# 21_DAC.net
KiCad netlist of a schematic drawn in Altium Designer
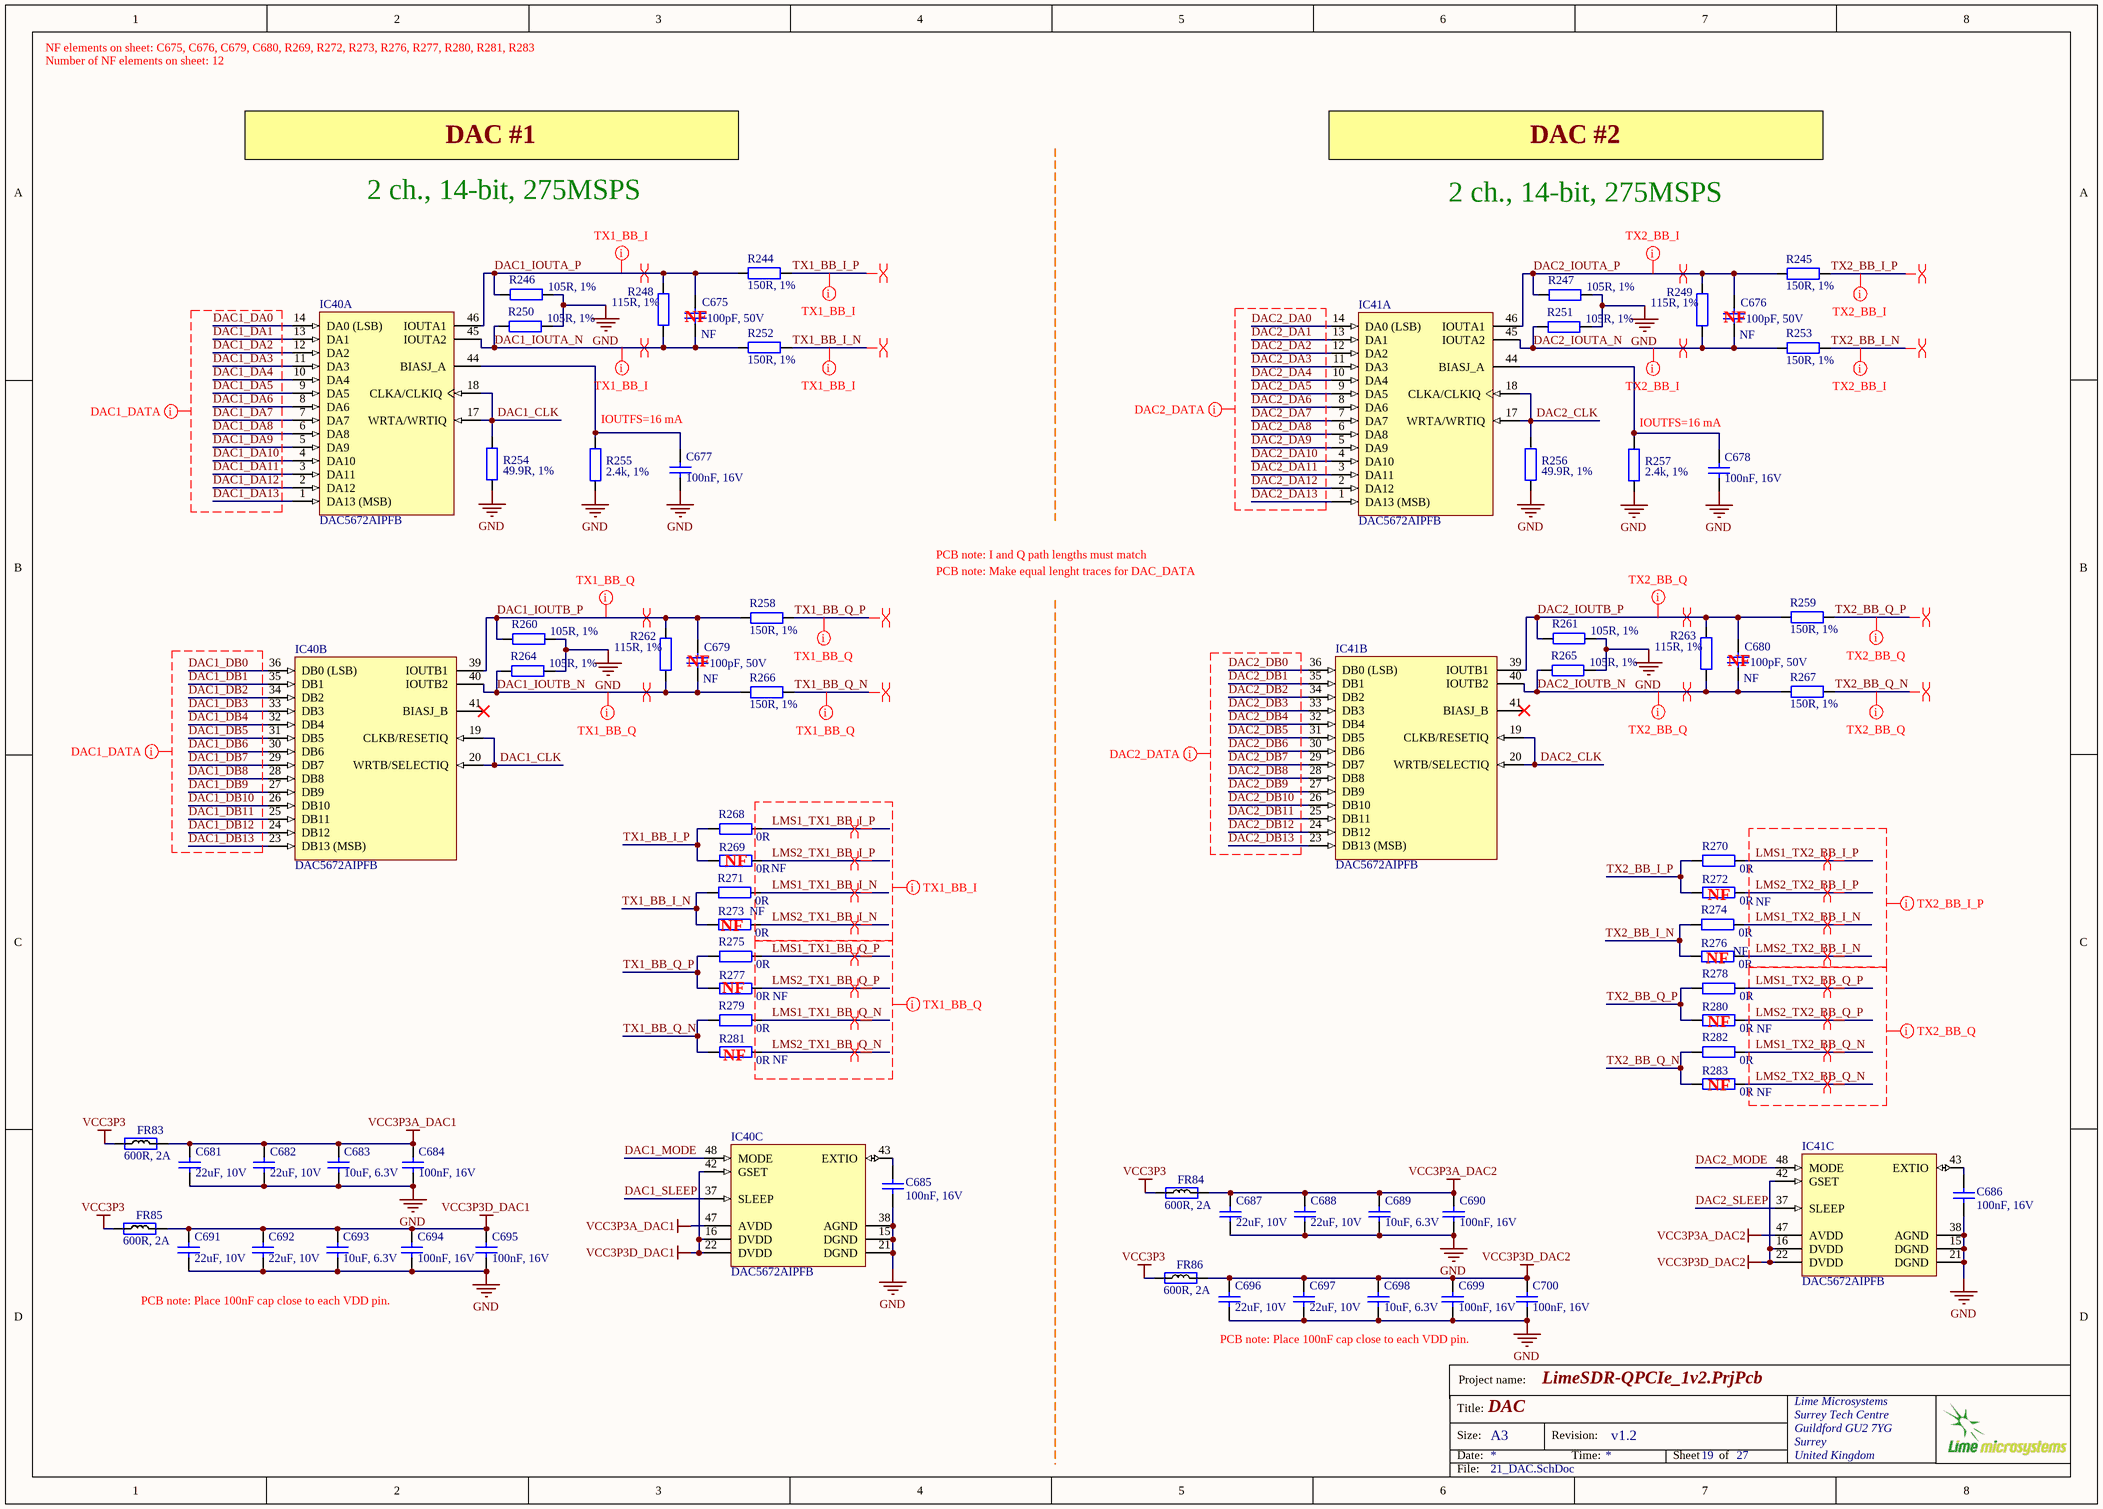
[diagram p0: 21_DAC.SchDoc]

(export (version "E")
  (design (tool "Eeschema 10.0.6"))
  (components
    (comp (ref "C675")
      (value "100pF, 50V")
      (footprint "CAP0402")
      (fields
        (field (name "ASSEMBLY INFO") "NF")
        (field (name "TOLERANCE") "±5%")
        (field (name "MANUFACTURER") "Yageo")
      )
      (libsource (lib "LimeMicroAltiumLib_schLib") (part "Cap_0402"))
    )
    (comp (ref "C676")
      (value "100pF, 50V")
      (footprint "CAP0402")
      (fields
        (field (name "ASSEMBLY INFO") "NF")
        (field (name "TOLERANCE") "±5%")
        (field (name "MANUFACTURER") "Yageo")
      )
      (libsource (lib "LimeMicroAltiumLib_schLib") (part "Cap_0402"))
    )
    (comp (ref "C677")
      (value "100nF, 16V")
      (footprint "CAP0402")
      (fields
        (field (name "TOLERANCE") "10 %")
        (field (name "MANUFACTURER") "Murata Electronics")
        (field (name "MANUFACTURER PART NUMBER") "GRM155R71C104KA88D")
      )
      (libsource (lib "LimeFPGAboard_schLib") (part "Cap_0603"))
    )
    (comp (ref "C678")
      (value "100nF, 16V")
      (footprint "CAP0402")
      (fields
        (field (name "TOLERANCE") "10 %")
        (field (name "MANUFACTURER") "Murata Electronics")
        (field (name "MANUFACTURER PART NUMBER") "GRM155R71C104KA88D")
      )
      (libsource (lib "LimeFPGAboard_schLib") (part "Cap_0603"))
    )
    (comp (ref "C679")
      (value "100pF, 50V")
      (footprint "CAP0402")
      (fields
        (field (name "ASSEMBLY INFO") "NF")
        (field (name "TOLERANCE") "±5%")
        (field (name "MANUFACTURER") "Yageo")
      )
      (libsource (lib "LimeMicroAltiumLib_schLib") (part "Cap_0402"))
    )
    (comp (ref "C680")
      (value "100pF, 50V")
      (footprint "CAP0402")
      (fields
        (field (name "ASSEMBLY INFO") "NF")
        (field (name "TOLERANCE") "±5%")
        (field (name "MANUFACTURER") "Yageo")
      )
      (libsource (lib "LimeMicroAltiumLib_schLib") (part "Cap_0402"))
    )
    (comp (ref "C681")
      (value "22uF, 10V")
      (footprint "CAP0603")
      (fields (field (name "TOLERANCE") "20 %") (field (name "MANUFACTURER") "TDK Corporation"))
      (libsource (lib "LimeFPGAboard_schLib") (part "Cap_0603"))
    )
    (comp (ref "C682")
      (value "22uF, 10V")
      (footprint "CAP0603")
      (fields (field (name "TOLERANCE") "20 %") (field (name "MANUFACTURER") "TDK Corporation"))
      (libsource (lib "LimeFPGAboard_schLib") (part "Cap_0603"))
    )
    (comp (ref "C683")
      (value "10uF, 6.3V")
      (footprint "CAP0603")
      (fields (field (name "TOLERANCE") "±20%") (field (name "MANUFACTURER") "Yageo"))
      (libsource (lib "LimeFPGAboard_schLib") (part "Cap_0603"))
    )
    (comp (ref "C684")
      (value "100nF, 16V")
      (footprint "CAP0402")
      (fields
        (field (name "TOLERANCE") "10 %")
        (field (name "MANUFACTURER") "Murata Electronics")
        (field (name "MANUFACTURER PART NUMBER") "GRM155R71C104KA88D")
      )
      (libsource (lib "LimeFPGAboard_schLib") (part "Cap_0603"))
    )
    (comp (ref "C685")
      (value "100nF, 16V")
      (footprint "CAP0402")
      (fields
        (field (name "TOLERANCE") "10 %")
        (field (name "MANUFACTURER") "Murata Electronics")
        (field (name "MANUFACTURER PART NUMBER") "GRM155R71C104KA88D")
      )
      (libsource (lib "LimeFPGAboard_schLib") (part "Cap_0603"))
    )
    (comp (ref "C686")
      (value "100nF, 16V")
      (footprint "CAP0402")
      (fields
        (field (name "TOLERANCE") "10 %")
        (field (name "MANUFACTURER") "Murata Electronics")
        (field (name "MANUFACTURER PART NUMBER") "GRM155R71C104KA88D")
      )
      (libsource (lib "LimeFPGAboard_schLib") (part "Cap_0603"))
    )
    (comp (ref "C687")
      (value "22uF, 10V")
      (footprint "CAP0603")
      (fields (field (name "TOLERANCE") "20 %") (field (name "MANUFACTURER") "TDK Corporation"))
      (libsource (lib "LimeFPGAboard_schLib") (part "Cap_0603"))
    )
    (comp (ref "C688")
      (value "22uF, 10V")
      (footprint "CAP0603")
      (fields (field (name "TOLERANCE") "20 %") (field (name "MANUFACTURER") "TDK Corporation"))
      (libsource (lib "LimeFPGAboard_schLib") (part "Cap_0603"))
    )
    (comp (ref "C689")
      (value "10uF, 6.3V")
      (footprint "CAP0603")
      (fields (field (name "TOLERANCE") "±20%") (field (name "MANUFACTURER") "Yageo"))
      (libsource (lib "LimeFPGAboard_schLib") (part "Cap_0603"))
    )
    (comp (ref "C690")
      (value "100nF, 16V")
      (footprint "CAP0402")
      (fields
        (field (name "TOLERANCE") "10 %")
        (field (name "MANUFACTURER") "Murata Electronics")
        (field (name "MANUFACTURER PART NUMBER") "GRM155R71C104KA88D")
      )
      (libsource (lib "LimeFPGAboard_schLib") (part "Cap_0603"))
    )
    (comp (ref "C691")
      (value "22uF, 10V")
      (footprint "CAP0603")
      (fields (field (name "TOLERANCE") "20 %") (field (name "MANUFACTURER") "TDK Corporation"))
      (libsource (lib "LimeFPGAboard_schLib") (part "Cap_0603"))
    )
    (comp (ref "C692")
      (value "22uF, 10V")
      (footprint "CAP0603")
      (fields (field (name "TOLERANCE") "20 %") (field (name "MANUFACTURER") "TDK Corporation"))
      (libsource (lib "LimeFPGAboard_schLib") (part "Cap_0603"))
    )
    (comp (ref "C693")
      (value "10uF, 6.3V")
      (footprint "CAP0603")
      (fields (field (name "TOLERANCE") "±20%") (field (name "MANUFACTURER") "Yageo"))
      (libsource (lib "LimeFPGAboard_schLib") (part "Cap_0603"))
    )
    (comp (ref "C694")
      (value "100nF, 16V")
      (footprint "CAP0402")
      (fields
        (field (name "TOLERANCE") "10 %")
        (field (name "MANUFACTURER") "Murata Electronics")
        (field (name "MANUFACTURER PART NUMBER") "GRM155R71C104KA88D")
      )
      (libsource (lib "LimeFPGAboard_schLib") (part "Cap_0603"))
    )
    (comp (ref "C695")
      (value "100nF, 16V")
      (footprint "CAP0402")
      (fields
        (field (name "TOLERANCE") "10 %")
        (field (name "MANUFACTURER") "Murata Electronics")
        (field (name "MANUFACTURER PART NUMBER") "GRM155R71C104KA88D")
      )
      (libsource (lib "LimeFPGAboard_schLib") (part "Cap_0603"))
    )
    (comp (ref "C696")
      (value "22uF, 10V")
      (footprint "CAP0603")
      (fields (field (name "TOLERANCE") "20 %") (field (name "MANUFACTURER") "TDK Corporation"))
      (libsource (lib "LimeFPGAboard_schLib") (part "Cap_0603"))
    )
    (comp (ref "C697")
      (value "22uF, 10V")
      (footprint "CAP0603")
      (fields (field (name "TOLERANCE") "20 %") (field (name "MANUFACTURER") "TDK Corporation"))
      (libsource (lib "LimeFPGAboard_schLib") (part "Cap_0603"))
    )
    (comp (ref "C698")
      (value "10uF, 6.3V")
      (footprint "CAP0603")
      (fields (field (name "TOLERANCE") "±20%") (field (name "MANUFACTURER") "Yageo"))
      (libsource (lib "LimeFPGAboard_schLib") (part "Cap_0603"))
    )
    (comp (ref "C699")
      (value "100nF, 16V")
      (footprint "CAP0402")
      (fields
        (field (name "TOLERANCE") "10 %")
        (field (name "MANUFACTURER") "Murata Electronics")
        (field (name "MANUFACTURER PART NUMBER") "GRM155R71C104KA88D")
      )
      (libsource (lib "LimeFPGAboard_schLib") (part "Cap_0603"))
    )
    (comp (ref "C700")
      (value "100nF, 16V")
      (footprint "CAP0402")
      (fields
        (field (name "TOLERANCE") "10 %")
        (field (name "MANUFACTURER") "Murata Electronics")
        (field (name "MANUFACTURER PART NUMBER") "GRM155R71C104KA88D")
      )
      (libsource (lib "LimeFPGAboard_schLib") (part "Cap_0603"))
    )
    (comp (ref "FR83")
      (value "600R, 2A")
      (footprint "RES0805")
      (fields (field (name "MANUFACTURER") "TDK"))
      (libsource (lib "LimeFPGAboard_schLib") (part "Ferrite"))
    )
    (comp (ref "FR84")
      (value "600R, 2A")
      (footprint "RES0805")
      (fields (field (name "MANUFACTURER") "TDK"))
      (libsource (lib "LimeFPGAboard_schLib") (part "Ferrite"))
    )
    (comp (ref "FR85")
      (value "600R, 2A")
      (footprint "RES0805")
      (fields (field (name "MANUFACTURER") "TDK"))
      (libsource (lib "LimeFPGAboard_schLib") (part "Ferrite"))
    )
    (comp (ref "FR86")
      (value "600R, 2A")
      (footprint "RES0805")
      (fields (field (name "MANUFACTURER") "TDK"))
      (libsource (lib "LimeFPGAboard_schLib") (part "Ferrite"))
    )
    (comp (ref "IC40")
      (value "DAC5672AIPFB")
      (footprint "TI-PFB48_L")
      (fields (field (name "MANUFACTURER") "Texas Instruments"))
      (libsource (lib "LimeMicroAltiumLib_schLib") (part "DAC5672AIPFB"))
    )
    (comp (ref "IC41")
      (value "DAC5672AIPFB")
      (footprint "TI-PFB48_L")
      (fields (field (name "MANUFACTURER") "Texas Instruments"))
      (libsource (lib "LimeMicroAltiumLib_schLib") (part "DAC5672AIPFB"))
    )
    (comp (ref "R244")
      (value "150R, 1%")
      (footprint "RES0402")
      (fields (field (name "MANUFACTURER") "Yageo") (field (name "TOLERANCE") "±1%"))
      (libsource (lib "LimeMicroAltiumLib_schLib") (part "Res_0402"))
    )
    (comp (ref "R245")
      (value "150R, 1%")
      (footprint "RES0402")
      (fields (field (name "MANUFACTURER") "Yageo") (field (name "TOLERANCE") "±1%"))
      (libsource (lib "LimeMicroAltiumLib_schLib") (part "Res_0402"))
    )
    (comp (ref "R246")
      (value "105R, 1%")
      (footprint "RES0402")
      (fields (field (name "TOLERANCE") "±1%") (field (name "MANUFACTURER") "Yageo"))
      (libsource (lib "LimeMicroAltiumLib_schLib") (part "Res_0402"))
    )
    (comp (ref "R247")
      (value "105R, 1%")
      (footprint "RES0402")
      (fields (field (name "TOLERANCE") "±1%") (field (name "MANUFACTURER") "Yageo"))
      (libsource (lib "LimeMicroAltiumLib_schLib") (part "Res_0402"))
    )
    (comp (ref "R248")
      (value "115R, 1%")
      (footprint "RES0402")
      (fields (field (name "MANUFACTURER") "Yageo") (field (name "TOLERANCE") "±1%"))
      (libsource (lib "LimeMicroAltiumLib_schLib") (part "Res_0402"))
    )
    (comp (ref "R249")
      (value "115R, 1%")
      (footprint "RES0402")
      (fields (field (name "MANUFACTURER") "Yageo") (field (name "TOLERANCE") "±1%"))
      (libsource (lib "LimeMicroAltiumLib_schLib") (part "Res_0402"))
    )
    (comp (ref "R250")
      (value "105R, 1%")
      (footprint "RES0402")
      (fields (field (name "TOLERANCE") "±1%") (field (name "MANUFACTURER") "Yageo"))
      (libsource (lib "LimeMicroAltiumLib_schLib") (part "Res_0402"))
    )
    (comp (ref "R251")
      (value "105R, 1%")
      (footprint "RES0402")
      (fields (field (name "TOLERANCE") "±1%") (field (name "MANUFACTURER") "Yageo"))
      (libsource (lib "LimeMicroAltiumLib_schLib") (part "Res_0402"))
    )
    (comp (ref "R252")
      (value "150R, 1%")
      (footprint "RES0402")
      (fields (field (name "MANUFACTURER") "Yageo") (field (name "TOLERANCE") "±1%"))
      (libsource (lib "LimeMicroAltiumLib_schLib") (part "Res_0402"))
    )
    (comp (ref "R253")
      (value "150R, 1%")
      (footprint "RES0402")
      (fields (field (name "MANUFACTURER") "Yageo") (field (name "TOLERANCE") "±1%"))
      (libsource (lib "LimeMicroAltiumLib_schLib") (part "Res_0402"))
    )
    (comp (ref "R254")
      (value "49.9R, 1%")
      (footprint "RES0402")
      (fields
        (field (name "TOLERANCE") "±1%")
        (field (name "MANUFACTURER") "Samsung Electro-Mechanics America, Inc.")
      )
      (libsource (lib "LimeMicroAltiumLib_schLib") (part "Res_0402"))
    )
    (comp (ref "R255")
      (value "2.4k, 1%")
      (footprint "RES0402")
      (fields
        (field (name "MANUFACTURER PART NUMBER") "RC0402FR-072K4L")
        (field (name "TOLERANCE") "±1%")
        (field (name "MANUFACTURER") "Yageo")
      )
      (libsource (lib "LimeMicroAltiumLib_schLib") (part "Res_0402"))
    )
    (comp (ref "R256")
      (value "49.9R, 1%")
      (footprint "RES0402")
      (fields
        (field (name "TOLERANCE") "±1%")
        (field (name "MANUFACTURER") "Samsung Electro-Mechanics America, Inc.")
      )
      (libsource (lib "LimeMicroAltiumLib_schLib") (part "Res_0402"))
    )
    (comp (ref "R257")
      (value "2.4k, 1%")
      (footprint "RES0402")
      (fields
        (field (name "MANUFACTURER PART NUMBER") "RC0402FR-072K4L")
        (field (name "TOLERANCE") "±1%")
        (field (name "MANUFACTURER") "Yageo")
      )
      (libsource (lib "LimeMicroAltiumLib_schLib") (part "Res_0402"))
    )
    (comp (ref "R258")
      (value "150R, 1%")
      (footprint "RES0402")
      (fields (field (name "MANUFACTURER") "Yageo") (field (name "TOLERANCE") "±1%"))
      (libsource (lib "LimeMicroAltiumLib_schLib") (part "Res_0402"))
    )
    (comp (ref "R259")
      (value "150R, 1%")
      (footprint "RES0402")
      (fields (field (name "MANUFACTURER") "Yageo") (field (name "TOLERANCE") "±1%"))
      (libsource (lib "LimeMicroAltiumLib_schLib") (part "Res_0402"))
    )
    (comp (ref "R260")
      (value "105R, 1%")
      (footprint "RES0402")
      (fields (field (name "TOLERANCE") "±1%") (field (name "MANUFACTURER") "Yageo"))
      (libsource (lib "LimeMicroAltiumLib_schLib") (part "Res_0402"))
    )
    (comp (ref "R261")
      (value "105R, 1%")
      (footprint "RES0402")
      (fields (field (name "TOLERANCE") "±1%") (field (name "MANUFACTURER") "Yageo"))
      (libsource (lib "LimeMicroAltiumLib_schLib") (part "Res_0402"))
    )
    (comp (ref "R262")
      (value "115R, 1%")
      (footprint "RES0402")
      (fields (field (name "MANUFACTURER") "Yageo") (field (name "TOLERANCE") "±1%"))
      (libsource (lib "LimeMicroAltiumLib_schLib") (part "Res_0402"))
    )
    (comp (ref "R263")
      (value "115R, 1%")
      (footprint "RES0402")
      (fields (field (name "MANUFACTURER") "Yageo") (field (name "TOLERANCE") "±1%"))
      (libsource (lib "LimeMicroAltiumLib_schLib") (part "Res_0402"))
    )
    (comp (ref "R264")
      (value "105R, 1%")
      (footprint "RES0402")
      (fields (field (name "TOLERANCE") "±1%") (field (name "MANUFACTURER") "Yageo"))
      (libsource (lib "LimeMicroAltiumLib_schLib") (part "Res_0402"))
    )
    (comp (ref "R265")
      (value "105R, 1%")
      (footprint "RES0402")
      (fields (field (name "TOLERANCE") "±1%") (field (name "MANUFACTURER") "Yageo"))
      (libsource (lib "LimeMicroAltiumLib_schLib") (part "Res_0402"))
    )
    (comp (ref "R266")
      (value "150R, 1%")
      (footprint "RES0402")
      (fields (field (name "MANUFACTURER") "Yageo") (field (name "TOLERANCE") "±1%"))
      (libsource (lib "LimeMicroAltiumLib_schLib") (part "Res_0402"))
    )
    (comp (ref "R267")
      (value "150R, 1%")
      (footprint "RES0402")
      (fields (field (name "MANUFACTURER") "Yageo") (field (name "TOLERANCE") "±1%"))
      (libsource (lib "LimeMicroAltiumLib_schLib") (part "Res_0402"))
    )
    (comp (ref "R268")
      (value "0R")
      (footprint "RES0402")
      (fields (field (name "MANUFACTURER") "Yageo"))
      (libsource (lib "LimeFPGAboard_schLib") (part "Res_0402"))
    )
    (comp (ref "R269")
      (value "0R")
      (footprint "RES0402")
      (fields (field (name "MANUFACTURER") "Yageo") (field (name "ASSEMBLY INFO") "NF"))
      (libsource (lib "LimeFPGAboard_schLib") (part "Res_0402"))
    )
    (comp (ref "R270")
      (value "0R")
      (footprint "RES0402")
      (fields (field (name "MANUFACTURER") "Yageo"))
      (libsource (lib "LimeFPGAboard_schLib") (part "Res_0402"))
    )
    (comp (ref "R271")
      (value "0R")
      (footprint "RES0402")
      (fields (field (name "MANUFACTURER") "Yageo"))
      (libsource (lib "LimeFPGAboard_schLib") (part "Res_0402"))
    )
    (comp (ref "R272")
      (value "0R")
      (footprint "RES0402")
      (fields (field (name "MANUFACTURER") "Yageo") (field (name "ASSEMBLY INFO") "NF"))
      (libsource (lib "LimeFPGAboard_schLib") (part "Res_0402"))
    )
    (comp (ref "R273")
      (value "0R")
      (footprint "RES0402")
      (fields (field (name "MANUFACTURER") "Yageo") (field (name "ASSEMBLY INFO") "NF"))
      (libsource (lib "LimeFPGAboard_schLib") (part "Res_0402"))
    )
    (comp (ref "R274")
      (value "0R")
      (footprint "RES0402")
      (fields (field (name "MANUFACTURER") "Yageo"))
      (libsource (lib "LimeFPGAboard_schLib") (part "Res_0402"))
    )
    (comp (ref "R275")
      (value "0R")
      (footprint "RES0402")
      (fields (field (name "MANUFACTURER") "Yageo"))
      (libsource (lib "LimeFPGAboard_schLib") (part "Res_0402"))
    )
    (comp (ref "R276")
      (value "0R")
      (footprint "RES0402")
      (fields (field (name "MANUFACTURER") "Yageo") (field (name "ASSEMBLY INFO") "NF"))
      (libsource (lib "LimeFPGAboard_schLib") (part "Res_0402"))
    )
    (comp (ref "R277")
      (value "0R")
      (footprint "RES0402")
      (fields (field (name "MANUFACTURER") "Yageo") (field (name "ASSEMBLY INFO") "NF"))
      (libsource (lib "LimeFPGAboard_schLib") (part "Res_0402"))
    )
    (comp (ref "R278")
      (value "0R")
      (footprint "RES0402")
      (fields (field (name "MANUFACTURER") "Yageo"))
      (libsource (lib "LimeFPGAboard_schLib") (part "Res_0402"))
    )
    (comp (ref "R279")
      (value "0R")
      (footprint "RES0402")
      (fields (field (name "MANUFACTURER") "Yageo"))
      (libsource (lib "LimeFPGAboard_schLib") (part "Res_0402"))
    )
    (comp (ref "R280")
      (value "0R")
      (footprint "RES0402")
      (fields (field (name "MANUFACTURER") "Yageo") (field (name "ASSEMBLY INFO") "NF"))
      (libsource (lib "LimeFPGAboard_schLib") (part "Res_0402"))
    )
    (comp (ref "R281")
      (value "0R")
      (footprint "RES0402")
      (fields (field (name "MANUFACTURER") "Yageo") (field (name "ASSEMBLY INFO") "NF"))
      (libsource (lib "LimeFPGAboard_schLib") (part "Res_0402"))
    )
    (comp (ref "R282")
      (value "0R")
      (footprint "RES0402")
      (fields (field (name "MANUFACTURER") "Yageo"))
      (libsource (lib "LimeFPGAboard_schLib") (part "Res_0402"))
    )
    (comp (ref "R283")
      (value "0R")
      (footprint "RES0402")
      (fields (field (name "MANUFACTURER") "Yageo") (field (name "ASSEMBLY INFO") "NF"))
      (libsource (lib "LimeFPGAboard_schLib") (part "Res_0402"))
    )
  )
  (nets
    (net (code "1") (name "/DAC1_CLK") (class "Default")
      (node (ref "IC40") (pin "17") (pinfunction "WRTA/WRTIQ_17") (pintype "input"))
      (node (ref "IC40") (pin "18") (pinfunction "CLKA/CLKIQ_18") (pintype "input"))
      (node (ref "IC40") (pin "19") (pinfunction "CLKB/RESETIQ_19") (pintype "input"))
      (node (ref "IC40") (pin "20") (pinfunction "WRTB/SELECTIQ_20") (pintype "input"))
      (node (ref "R254") (pin "2") (pinfunction "2_2") (pintype "passive"))
    )
    (net (code "2") (name "/DAC1_DA0") (class "Default")
      (node (ref "IC40") (pin "14") (pinfunction "DA0_(LSB)_14") (pintype "input"))
    )
    (net (code "3") (name "/DAC1_DA1") (class "Default")
      (node (ref "IC40") (pin "13") (pinfunction "DA1_13") (pintype "input"))
    )
    (net (code "4") (name "/DAC1_DA2") (class "Default")
      (node (ref "IC40") (pin "12") (pinfunction "DA2_12") (pintype "input"))
    )
    (net (code "5") (name "/DAC1_DA3") (class "Default")
      (node (ref "IC40") (pin "11") (pinfunction "DA3_11") (pintype "input"))
    )
    (net (code "6") (name "/DAC1_DA4") (class "Default")
      (node (ref "IC40") (pin "10") (pinfunction "DA4_10") (pintype "input"))
    )
    (net (code "7") (name "/DAC1_DA5") (class "Default")
      (node (ref "IC40") (pin "9") (pinfunction "DA5_9") (pintype "input"))
    )
    (net (code "8") (name "/DAC1_DA6") (class "Default")
      (node (ref "IC40") (pin "8") (pinfunction "DA6_8") (pintype "input"))
    )
    (net (code "9") (name "/DAC1_DA7") (class "Default")
      (node (ref "IC40") (pin "7") (pinfunction "DA7_7") (pintype "input"))
    )
    (net (code "10") (name "/DAC1_DA8") (class "Default")
      (node (ref "IC40") (pin "6") (pinfunction "DA8_6") (pintype "input"))
    )
    (net (code "11") (name "/DAC1_DA9") (class "Default")
      (node (ref "IC40") (pin "5") (pinfunction "DA9_5") (pintype "input"))
    )
    (net (code "12") (name "/DAC1_DA10") (class "Default")
      (node (ref "IC40") (pin "4") (pinfunction "DA10_4") (pintype "input"))
    )
    (net (code "13") (name "/DAC1_DA11") (class "Default")
      (node (ref "IC40") (pin "3") (pinfunction "DA11_3") (pintype "input"))
    )
    (net (code "14") (name "/DAC1_DA12") (class "Default")
      (node (ref "IC40") (pin "2") (pinfunction "DA12_2") (pintype "input"))
    )
    (net (code "15") (name "/DAC1_DA13") (class "Default")
      (node (ref "IC40") (pin "1") (pinfunction "DA13_(MSB)_1") (pintype "input"))
    )
    (net (code "16") (name "/DAC1_DB0") (class "Default")
      (node (ref "IC40") (pin "36") (pinfunction "DB0_(LSB)_36") (pintype "input"))
    )
    (net (code "17") (name "/DAC1_DB1") (class "Default")
      (node (ref "IC40") (pin "35") (pinfunction "DB1_35") (pintype "input"))
    )
    (net (code "18") (name "/DAC1_DB2") (class "Default")
      (node (ref "IC40") (pin "34") (pinfunction "DB2_34") (pintype "input"))
    )
    (net (code "19") (name "/DAC1_DB3") (class "Default")
      (node (ref "IC40") (pin "33") (pinfunction "DB3_33") (pintype "input"))
    )
    (net (code "20") (name "/DAC1_DB4") (class "Default")
      (node (ref "IC40") (pin "32") (pinfunction "DB4_32") (pintype "input"))
    )
    (net (code "21") (name "/DAC1_DB5") (class "Default")
      (node (ref "IC40") (pin "31") (pinfunction "DB5_31") (pintype "input"))
    )
    (net (code "22") (name "/DAC1_DB6") (class "Default")
      (node (ref "IC40") (pin "30") (pinfunction "DB6_30") (pintype "input"))
    )
    (net (code "23") (name "/DAC1_DB7") (class "Default")
      (node (ref "IC40") (pin "29") (pinfunction "DB7_29") (pintype "input"))
    )
    (net (code "24") (name "/DAC1_DB8") (class "Default")
      (node (ref "IC40") (pin "28") (pinfunction "DB8_28") (pintype "input"))
    )
    (net (code "25") (name "/DAC1_DB9") (class "Default")
      (node (ref "IC40") (pin "27") (pinfunction "DB9_27") (pintype "input"))
    )
    (net (code "26") (name "/DAC1_DB10") (class "Default")
      (node (ref "IC40") (pin "26") (pinfunction "DB10_26") (pintype "input"))
    )
    (net (code "27") (name "/DAC1_DB11") (class "Default")
      (node (ref "IC40") (pin "25") (pinfunction "DB11_25") (pintype "input"))
    )
    (net (code "28") (name "/DAC1_DB12") (class "Default")
      (node (ref "IC40") (pin "24") (pinfunction "DB12_24") (pintype "input"))
    )
    (net (code "29") (name "/DAC1_DB13") (class "Default")
      (node (ref "IC40") (pin "23") (pinfunction "DB13_(MSB)_23") (pintype "input"))
    )
    (net (code "30") (name "/DAC1_IOUTA_N") (class "Default")
      (node (ref "C675") (pin "2") (pinfunction "2_2") (pintype "passive"))
      (node (ref "IC40") (pin "45") (pinfunction "IOUTA2_45") (pintype "tri_state"))
      (node (ref "R248") (pin "2") (pinfunction "2_2") (pintype "passive"))
      (node (ref "R250") (pin "1") (pinfunction "1_1") (pintype "passive"))
      (node (ref "R252") (pin "1") (pinfunction "1_1") (pintype "passive"))
    )
    (net (code "31") (name "/DAC1_IOUTA_P") (class "Default")
      (node (ref "C675") (pin "1") (pinfunction "1_1") (pintype "passive"))
      (node (ref "IC40") (pin "46") (pinfunction "IOUTA1_46") (pintype "tri_state"))
      (node (ref "R244") (pin "1") (pinfunction "1_1") (pintype "passive"))
      (node (ref "R246") (pin "1") (pinfunction "1_1") (pintype "passive"))
      (node (ref "R248") (pin "1") (pinfunction "1_1") (pintype "passive"))
    )
    (net (code "32") (name "/DAC1_IOUTB_N") (class "Default")
      (node (ref "C679") (pin "2") (pinfunction "2_2") (pintype "passive"))
      (node (ref "IC40") (pin "40") (pinfunction "IOUTB2_40") (pintype "tri_state"))
      (node (ref "R262") (pin "2") (pinfunction "2_2") (pintype "passive"))
      (node (ref "R264") (pin "1") (pinfunction "1_1") (pintype "passive"))
      (node (ref "R266") (pin "1") (pinfunction "1_1") (pintype "passive"))
    )
    (net (code "33") (name "/DAC1_IOUTB_P") (class "Default")
      (node (ref "C679") (pin "1") (pinfunction "1_1") (pintype "passive"))
      (node (ref "IC40") (pin "39") (pinfunction "IOUTB1_39") (pintype "tri_state"))
      (node (ref "R258") (pin "1") (pinfunction "1_1") (pintype "passive"))
      (node (ref "R260") (pin "1") (pinfunction "1_1") (pintype "passive"))
      (node (ref "R262") (pin "1") (pinfunction "1_1") (pintype "passive"))
    )
    (net (code "34") (name "/DAC1_MODE") (class "Default")
      (node (ref "IC40") (pin "48") (pinfunction "MODE_48") (pintype "input"))
    )
    (net (code "35") (name "/DAC1_SLEEP") (class "Default")
      (node (ref "IC40") (pin "37") (pinfunction "SLEEP_37") (pintype "input"))
    )
    (net (code "36") (name "/DAC2_CLK") (class "Default")
      (node (ref "IC41") (pin "17") (pinfunction "WRTA/WRTIQ_17") (pintype "input"))
      (node (ref "IC41") (pin "18") (pinfunction "CLKA/CLKIQ_18") (pintype "input"))
      (node (ref "IC41") (pin "19") (pinfunction "CLKB/RESETIQ_19") (pintype "input"))
      (node (ref "IC41") (pin "20") (pinfunction "WRTB/SELECTIQ_20") (pintype "input"))
      (node (ref "R256") (pin "2") (pinfunction "2_2") (pintype "passive"))
    )
    (net (code "37") (name "/DAC2_DA0") (class "Default")
      (node (ref "IC41") (pin "14") (pinfunction "DA0_(LSB)_14") (pintype "input"))
    )
    (net (code "38") (name "/DAC2_DA1") (class "Default")
      (node (ref "IC41") (pin "13") (pinfunction "DA1_13") (pintype "input"))
    )
    (net (code "39") (name "/DAC2_DA2") (class "Default")
      (node (ref "IC41") (pin "12") (pinfunction "DA2_12") (pintype "input"))
    )
    (net (code "40") (name "/DAC2_DA3") (class "Default")
      (node (ref "IC41") (pin "11") (pinfunction "DA3_11") (pintype "input"))
    )
    (net (code "41") (name "/DAC2_DA4") (class "Default")
      (node (ref "IC41") (pin "10") (pinfunction "DA4_10") (pintype "input"))
    )
    (net (code "42") (name "/DAC2_DA5") (class "Default")
      (node (ref "IC41") (pin "9") (pinfunction "DA5_9") (pintype "input"))
    )
    (net (code "43") (name "/DAC2_DA6") (class "Default")
      (node (ref "IC41") (pin "8") (pinfunction "DA6_8") (pintype "input"))
    )
    (net (code "44") (name "/DAC2_DA7") (class "Default")
      (node (ref "IC41") (pin "7") (pinfunction "DA7_7") (pintype "input"))
    )
    (net (code "45") (name "/DAC2_DA8") (class "Default")
      (node (ref "IC41") (pin "6") (pinfunction "DA8_6") (pintype "input"))
    )
    (net (code "46") (name "/DAC2_DA9") (class "Default")
      (node (ref "IC41") (pin "5") (pinfunction "DA9_5") (pintype "input"))
    )
    (net (code "47") (name "/DAC2_DA10") (class "Default")
      (node (ref "IC41") (pin "4") (pinfunction "DA10_4") (pintype "input"))
    )
    (net (code "48") (name "/DAC2_DA11") (class "Default")
      (node (ref "IC41") (pin "3") (pinfunction "DA11_3") (pintype "input"))
    )
    (net (code "49") (name "/DAC2_DA12") (class "Default")
      (node (ref "IC41") (pin "2") (pinfunction "DA12_2") (pintype "input"))
    )
    (net (code "50") (name "/DAC2_DA13") (class "Default")
      (node (ref "IC41") (pin "1") (pinfunction "DA13_(MSB)_1") (pintype "input"))
    )
    (net (code "51") (name "/DAC2_DB0") (class "Default")
      (node (ref "IC41") (pin "36") (pinfunction "DB0_(LSB)_36") (pintype "input"))
    )
    (net (code "52") (name "/DAC2_DB1") (class "Default")
      (node (ref "IC41") (pin "35") (pinfunction "DB1_35") (pintype "input"))
    )
    (net (code "53") (name "/DAC2_DB2") (class "Default")
      (node (ref "IC41") (pin "34") (pinfunction "DB2_34") (pintype "input"))
    )
    (net (code "54") (name "/DAC2_DB3") (class "Default")
      (node (ref "IC41") (pin "33") (pinfunction "DB3_33") (pintype "input"))
    )
    (net (code "55") (name "/DAC2_DB4") (class "Default")
      (node (ref "IC41") (pin "32") (pinfunction "DB4_32") (pintype "input"))
    )
    (net (code "56") (name "/DAC2_DB5") (class "Default")
      (node (ref "IC41") (pin "31") (pinfunction "DB5_31") (pintype "input"))
    )
    (net (code "57") (name "/DAC2_DB6") (class "Default")
      (node (ref "IC41") (pin "30") (pinfunction "DB6_30") (pintype "input"))
    )
    (net (code "58") (name "/DAC2_DB7") (class "Default")
      (node (ref "IC41") (pin "29") (pinfunction "DB7_29") (pintype "input"))
    )
    (net (code "59") (name "/DAC2_DB8") (class "Default")
      (node (ref "IC41") (pin "28") (pinfunction "DB8_28") (pintype "input"))
    )
    (net (code "60") (name "/DAC2_DB9") (class "Default")
      (node (ref "IC41") (pin "27") (pinfunction "DB9_27") (pintype "input"))
    )
    (net (code "61") (name "/DAC2_DB10") (class "Default")
      (node (ref "IC41") (pin "26") (pinfunction "DB10_26") (pintype "input"))
    )
    (net (code "62") (name "/DAC2_DB11") (class "Default")
      (node (ref "IC41") (pin "25") (pinfunction "DB11_25") (pintype "input"))
    )
    (net (code "63") (name "/DAC2_DB12") (class "Default")
      (node (ref "IC41") (pin "24") (pinfunction "DB12_24") (pintype "input"))
    )
    (net (code "64") (name "/DAC2_DB13") (class "Default")
      (node (ref "IC41") (pin "23") (pinfunction "DB13_(MSB)_23") (pintype "input"))
    )
    (net (code "65") (name "/DAC2_IOUTA_N") (class "Default")
      (node (ref "C676") (pin "2") (pinfunction "2_2") (pintype "passive"))
      (node (ref "IC41") (pin "45") (pinfunction "IOUTA2_45") (pintype "tri_state"))
      (node (ref "R249") (pin "2") (pinfunction "2_2") (pintype "passive"))
      (node (ref "R251") (pin "1") (pinfunction "1_1") (pintype "passive"))
      (node (ref "R253") (pin "1") (pinfunction "1_1") (pintype "passive"))
    )
    (net (code "66") (name "/DAC2_IOUTA_P") (class "Default")
      (node (ref "C676") (pin "1") (pinfunction "1_1") (pintype "passive"))
      (node (ref "IC41") (pin "46") (pinfunction "IOUTA1_46") (pintype "tri_state"))
      (node (ref "R245") (pin "1") (pinfunction "1_1") (pintype "passive"))
      (node (ref "R247") (pin "1") (pinfunction "1_1") (pintype "passive"))
      (node (ref "R249") (pin "1") (pinfunction "1_1") (pintype "passive"))
    )
    (net (code "67") (name "/DAC2_IOUTB_N") (class "Default")
      (node (ref "C680") (pin "2") (pinfunction "2_2") (pintype "passive"))
      (node (ref "IC41") (pin "40") (pinfunction "IOUTB2_40") (pintype "tri_state"))
      (node (ref "R263") (pin "2") (pinfunction "2_2") (pintype "passive"))
      (node (ref "R265") (pin "1") (pinfunction "1_1") (pintype "passive"))
      (node (ref "R267") (pin "1") (pinfunction "1_1") (pintype "passive"))
    )
    (net (code "68") (name "/DAC2_IOUTB_P") (class "Default")
      (node (ref "C680") (pin "1") (pinfunction "1_1") (pintype "passive"))
      (node (ref "IC41") (pin "39") (pinfunction "IOUTB1_39") (pintype "tri_state"))
      (node (ref "R259") (pin "1") (pinfunction "1_1") (pintype "passive"))
      (node (ref "R261") (pin "1") (pinfunction "1_1") (pintype "passive"))
      (node (ref "R263") (pin "1") (pinfunction "1_1") (pintype "passive"))
    )
    (net (code "69") (name "/DAC2_MODE") (class "Default")
      (node (ref "IC41") (pin "48") (pinfunction "MODE_48") (pintype "input"))
    )
    (net (code "70") (name "/DAC2_SLEEP") (class "Default")
      (node (ref "IC41") (pin "37") (pinfunction "SLEEP_37") (pintype "input"))
    )
    (net (code "71") (name "/LMS1_TX1_BB_I_N") (class "Default")
      (node (ref "R271") (pin "1") (pinfunction "1_1") (pintype "passive"))
    )
    (net (code "72") (name "/LMS1_TX1_BB_I_P") (class "Default")
      (node (ref "R268") (pin "1") (pinfunction "1_1") (pintype "passive"))
    )
    (net (code "73") (name "/LMS1_TX1_BB_Q_N") (class "Default")
      (node (ref "R279") (pin "1") (pinfunction "1_1") (pintype "passive"))
    )
    (net (code "74") (name "/LMS1_TX1_BB_Q_P") (class "Default")
      (node (ref "R275") (pin "1") (pinfunction "1_1") (pintype "passive"))
    )
    (net (code "75") (name "/LMS1_TX2_BB_I_N") (class "Default")
      (node (ref "R274") (pin "1") (pinfunction "1_1") (pintype "passive"))
    )
    (net (code "76") (name "/LMS1_TX2_BB_I_P") (class "Default")
      (node (ref "R270") (pin "1") (pinfunction "1_1") (pintype "passive"))
    )
    (net (code "77") (name "/LMS1_TX2_BB_Q_N") (class "Default")
      (node (ref "R282") (pin "1") (pinfunction "1_1") (pintype "passive"))
    )
    (net (code "78") (name "/LMS1_TX2_BB_Q_P") (class "Default")
      (node (ref "R278") (pin "1") (pinfunction "1_1") (pintype "passive"))
    )
    (net (code "79") (name "/LMS2_TX1_BB_I_N") (class "Default")
      (node (ref "R273") (pin "1") (pinfunction "1_1") (pintype "passive"))
    )
    (net (code "80") (name "/LMS2_TX1_BB_I_P") (class "Default")
      (node (ref "R269") (pin "1") (pinfunction "1_1") (pintype "passive"))
    )
    (net (code "81") (name "/LMS2_TX1_BB_Q_N") (class "Default")
      (node (ref "R281") (pin "1") (pinfunction "1_1") (pintype "passive"))
    )
    (net (code "82") (name "/LMS2_TX1_BB_Q_P") (class "Default")
      (node (ref "R277") (pin "1") (pinfunction "1_1") (pintype "passive"))
    )
    (net (code "83") (name "/LMS2_TX2_BB_I_N") (class "Default")
      (node (ref "R276") (pin "1") (pinfunction "1_1") (pintype "passive"))
    )
    (net (code "84") (name "/LMS2_TX2_BB_I_P") (class "Default")
      (node (ref "R272") (pin "1") (pinfunction "1_1") (pintype "passive"))
    )
    (net (code "85") (name "/LMS2_TX2_BB_Q_N") (class "Default")
      (node (ref "R283") (pin "1") (pinfunction "1_1") (pintype "passive"))
    )
    (net (code "86") (name "/LMS2_TX2_BB_Q_P") (class "Default")
      (node (ref "R280") (pin "1") (pinfunction "1_1") (pintype "passive"))
    )
    (net (code "87") (name "/TX1_BB_I_N") (class "Default")
      (node (ref "R252") (pin "2") (pinfunction "2_2") (pintype "passive"))
      (node (ref "R271") (pin "2") (pinfunction "2_2") (pintype "passive"))
      (node (ref "R273") (pin "2") (pinfunction "2_2") (pintype "passive"))
    )
    (net (code "88") (name "/TX1_BB_I_P") (class "Default")
      (node (ref "R244") (pin "2") (pinfunction "2_2") (pintype "passive"))
      (node (ref "R268") (pin "2") (pinfunction "2_2") (pintype "passive"))
      (node (ref "R269") (pin "2") (pinfunction "2_2") (pintype "passive"))
    )
    (net (code "89") (name "/TX1_BB_Q_N") (class "Default")
      (node (ref "R266") (pin "2") (pinfunction "2_2") (pintype "passive"))
      (node (ref "R279") (pin "2") (pinfunction "2_2") (pintype "passive"))
      (node (ref "R281") (pin "2") (pinfunction "2_2") (pintype "passive"))
    )
    (net (code "90") (name "/TX1_BB_Q_P") (class "Default")
      (node (ref "R258") (pin "2") (pinfunction "2_2") (pintype "passive"))
      (node (ref "R275") (pin "2") (pinfunction "2_2") (pintype "passive"))
      (node (ref "R277") (pin "2") (pinfunction "2_2") (pintype "passive"))
    )
    (net (code "91") (name "/TX2_BB_I_N") (class "Default")
      (node (ref "R253") (pin "2") (pinfunction "2_2") (pintype "passive"))
      (node (ref "R274") (pin "2") (pinfunction "2_2") (pintype "passive"))
      (node (ref "R276") (pin "2") (pinfunction "2_2") (pintype "passive"))
    )
    (net (code "92") (name "/TX2_BB_I_P") (class "Default")
      (node (ref "R245") (pin "2") (pinfunction "2_2") (pintype "passive"))
      (node (ref "R270") (pin "2") (pinfunction "2_2") (pintype "passive"))
      (node (ref "R272") (pin "2") (pinfunction "2_2") (pintype "passive"))
    )
    (net (code "93") (name "/TX2_BB_Q_N") (class "Default")
      (node (ref "R267") (pin "2") (pinfunction "2_2") (pintype "passive"))
      (node (ref "R282") (pin "2") (pinfunction "2_2") (pintype "passive"))
      (node (ref "R283") (pin "2") (pinfunction "2_2") (pintype "passive"))
    )
    (net (code "94") (name "/TX2_BB_Q_P") (class "Default")
      (node (ref "R259") (pin "2") (pinfunction "2_2") (pintype "passive"))
      (node (ref "R278") (pin "2") (pinfunction "2_2") (pintype "passive"))
      (node (ref "R280") (pin "2") (pinfunction "2_2") (pintype "passive"))
    )
    (net (code "95") (name "GND") (class "Default")
      (node (ref "C677") (pin "1") (pinfunction "1_1") (pintype "passive"))
      (node (ref "C678") (pin "1") (pinfunction "1_1") (pintype "passive"))
      (node (ref "C681") (pin "1") (pinfunction "1_1") (pintype "passive"))
      (node (ref "C682") (pin "1") (pinfunction "1_1") (pintype "passive"))
      (node (ref "C683") (pin "1") (pinfunction "1_1") (pintype "passive"))
      (node (ref "C684") (pin "1") (pinfunction "1_1") (pintype "passive"))
      (node (ref "C685") (pin "1") (pinfunction "1_1") (pintype "passive"))
      (node (ref "C686") (pin "1") (pinfunction "1_1") (pintype "passive"))
      (node (ref "C687") (pin "1") (pinfunction "1_1") (pintype "passive"))
      (node (ref "C688") (pin "1") (pinfunction "1_1") (pintype "passive"))
      (node (ref "C689") (pin "1") (pinfunction "1_1") (pintype "passive"))
      (node (ref "C690") (pin "1") (pinfunction "1_1") (pintype "passive"))
      (node (ref "C691") (pin "1") (pinfunction "1_1") (pintype "passive"))
      (node (ref "C692") (pin "1") (pinfunction "1_1") (pintype "passive"))
      (node (ref "C693") (pin "1") (pinfunction "1_1") (pintype "passive"))
      (node (ref "C694") (pin "1") (pinfunction "1_1") (pintype "passive"))
      (node (ref "C695") (pin "1") (pinfunction "1_1") (pintype "passive"))
      (node (ref "C696") (pin "1") (pinfunction "1_1") (pintype "passive"))
      (node (ref "C697") (pin "1") (pinfunction "1_1") (pintype "passive"))
      (node (ref "C698") (pin "1") (pinfunction "1_1") (pintype "passive"))
      (node (ref "C699") (pin "1") (pinfunction "1_1") (pintype "passive"))
      (node (ref "C700") (pin "1") (pinfunction "1_1") (pintype "passive"))
      (node (ref "IC40") (pin "15") (pinfunction "DGND_15") (pintype "power_in"))
      (node (ref "IC40") (pin "21") (pinfunction "DGND_21") (pintype "power_in"))
      (node (ref "IC40") (pin "38") (pinfunction "AGND_38") (pintype "power_in"))
      (node (ref "IC41") (pin "15") (pinfunction "DGND_15") (pintype "power_in"))
      (node (ref "IC41") (pin "21") (pinfunction "DGND_21") (pintype "power_in"))
      (node (ref "IC41") (pin "38") (pinfunction "AGND_38") (pintype "power_in"))
      (node (ref "R246") (pin "2") (pinfunction "2_2") (pintype "passive"))
      (node (ref "R247") (pin "2") (pinfunction "2_2") (pintype "passive"))
      (node (ref "R250") (pin "2") (pinfunction "2_2") (pintype "passive"))
      (node (ref "R251") (pin "2") (pinfunction "2_2") (pintype "passive"))
      (node (ref "R254") (pin "1") (pinfunction "1_1") (pintype "passive"))
      (node (ref "R255") (pin "1") (pinfunction "1_1") (pintype "passive"))
      (node (ref "R256") (pin "1") (pinfunction "1_1") (pintype "passive"))
      (node (ref "R257") (pin "1") (pinfunction "1_1") (pintype "passive"))
      (node (ref "R260") (pin "2") (pinfunction "2_2") (pintype "passive"))
      (node (ref "R261") (pin "2") (pinfunction "2_2") (pintype "passive"))
      (node (ref "R264") (pin "2") (pinfunction "2_2") (pintype "passive"))
      (node (ref "R265") (pin "2") (pinfunction "2_2") (pintype "passive"))
    )
    (net (code "96") (name "Net-(IC40A-BIASJ_A)") (class "Default")
      (node (ref "C677") (pin "2") (pinfunction "2_2") (pintype "passive"))
      (node (ref "IC40") (pin "44") (pinfunction "BIASJ_A_44") (pintype "passive"))
      (node (ref "R255") (pin "2") (pinfunction "2_2") (pintype "passive"))
    )
    (net (code "97") (name "Net-(IC40C-EXTIO)") (class "Default")
      (node (ref "C685") (pin "2") (pinfunction "2_2") (pintype "passive"))
      (node (ref "IC40") (pin "43") (pinfunction "EXTIO_43") (pintype "bidirectional"))
    )
    (net (code "98") (name "Net-(IC41A-BIASJ_A)") (class "Default")
      (node (ref "C678") (pin "2") (pinfunction "2_2") (pintype "passive"))
      (node (ref "IC41") (pin "44") (pinfunction "BIASJ_A_44") (pintype "passive"))
      (node (ref "R257") (pin "2") (pinfunction "2_2") (pintype "passive"))
    )
    (net (code "99") (name "Net-(IC41C-EXTIO)") (class "Default")
      (node (ref "C686") (pin "2") (pinfunction "2_2") (pintype "passive"))
      (node (ref "IC41") (pin "43") (pinfunction "EXTIO_43") (pintype "bidirectional"))
    )
    (net (code "100") (name "VCC3P3") (class "Default")
      (node (ref "FR83") (pin "1") (pinfunction "1_1") (pintype "passive"))
      (node (ref "FR84") (pin "1") (pinfunction "1_1") (pintype "passive"))
      (node (ref "FR85") (pin "1") (pinfunction "1_1") (pintype "passive"))
      (node (ref "FR86") (pin "1") (pinfunction "1_1") (pintype "passive"))
    )
    (net (code "101") (name "VCC3P3A_DAC1") (class "Default")
      (node (ref "C681") (pin "2") (pinfunction "2_2") (pintype "passive"))
      (node (ref "C682") (pin "2") (pinfunction "2_2") (pintype "passive"))
      (node (ref "C683") (pin "2") (pinfunction "2_2") (pintype "passive"))
      (node (ref "C684") (pin "2") (pinfunction "2_2") (pintype "passive"))
      (node (ref "FR83") (pin "2") (pinfunction "2_2") (pintype "passive"))
      (node (ref "IC40") (pin "47") (pinfunction "AVDD_47") (pintype "power_in"))
    )
    (net (code "102") (name "VCC3P3A_DAC2") (class "Default")
      (node (ref "C687") (pin "2") (pinfunction "2_2") (pintype "passive"))
      (node (ref "C688") (pin "2") (pinfunction "2_2") (pintype "passive"))
      (node (ref "C689") (pin "2") (pinfunction "2_2") (pintype "passive"))
      (node (ref "C690") (pin "2") (pinfunction "2_2") (pintype "passive"))
      (node (ref "FR84") (pin "2") (pinfunction "2_2") (pintype "passive"))
      (node (ref "IC41") (pin "47") (pinfunction "AVDD_47") (pintype "power_in"))
    )
    (net (code "103") (name "VCC3P3D_DAC1") (class "Default")
      (node (ref "C691") (pin "2") (pinfunction "2_2") (pintype "passive"))
      (node (ref "C692") (pin "2") (pinfunction "2_2") (pintype "passive"))
      (node (ref "C693") (pin "2") (pinfunction "2_2") (pintype "passive"))
      (node (ref "C694") (pin "2") (pinfunction "2_2") (pintype "passive"))
      (node (ref "C695") (pin "2") (pinfunction "2_2") (pintype "passive"))
      (node (ref "FR85") (pin "2") (pinfunction "2_2") (pintype "passive"))
      (node (ref "IC40") (pin "16") (pinfunction "DVDD_16") (pintype "power_in"))
      (node (ref "IC40") (pin "22") (pinfunction "DVDD_22") (pintype "power_in"))
      (node (ref "IC40") (pin "42") (pinfunction "GSET_42") (pintype "input"))
    )
    (net (code "104") (name "VCC3P3D_DAC2") (class "Default")
      (node (ref "C696") (pin "2") (pinfunction "2_2") (pintype "passive"))
      (node (ref "C697") (pin "2") (pinfunction "2_2") (pintype "passive"))
      (node (ref "C698") (pin "2") (pinfunction "2_2") (pintype "passive"))
      (node (ref "C699") (pin "2") (pinfunction "2_2") (pintype "passive"))
      (node (ref "C700") (pin "2") (pinfunction "2_2") (pintype "passive"))
      (node (ref "FR86") (pin "2") (pinfunction "2_2") (pintype "passive"))
      (node (ref "IC41") (pin "16") (pinfunction "DVDD_16") (pintype "power_in"))
      (node (ref "IC41") (pin "22") (pinfunction "DVDD_22") (pintype "power_in"))
      (node (ref "IC41") (pin "42") (pinfunction "GSET_42") (pintype "input"))
    )
    (net (code "105") (name "unconnected-(IC40B-BIASJ_B-Pad41)") (class "Default")
      (node (ref "IC40") (pin "41") (pinfunction "BIASJ_B_41") (pintype "passive+no_connect"))
    )
    (net (code "106") (name "unconnected-(IC41B-BIASJ_B-Pad41)") (class "Default")
      (node (ref "IC41") (pin "41") (pinfunction "BIASJ_B_41") (pintype "passive+no_connect"))
    )
  )
)
